# UmbilicalBoardV2.net
KiCad netlist of a schematic drawn in Altium Designer
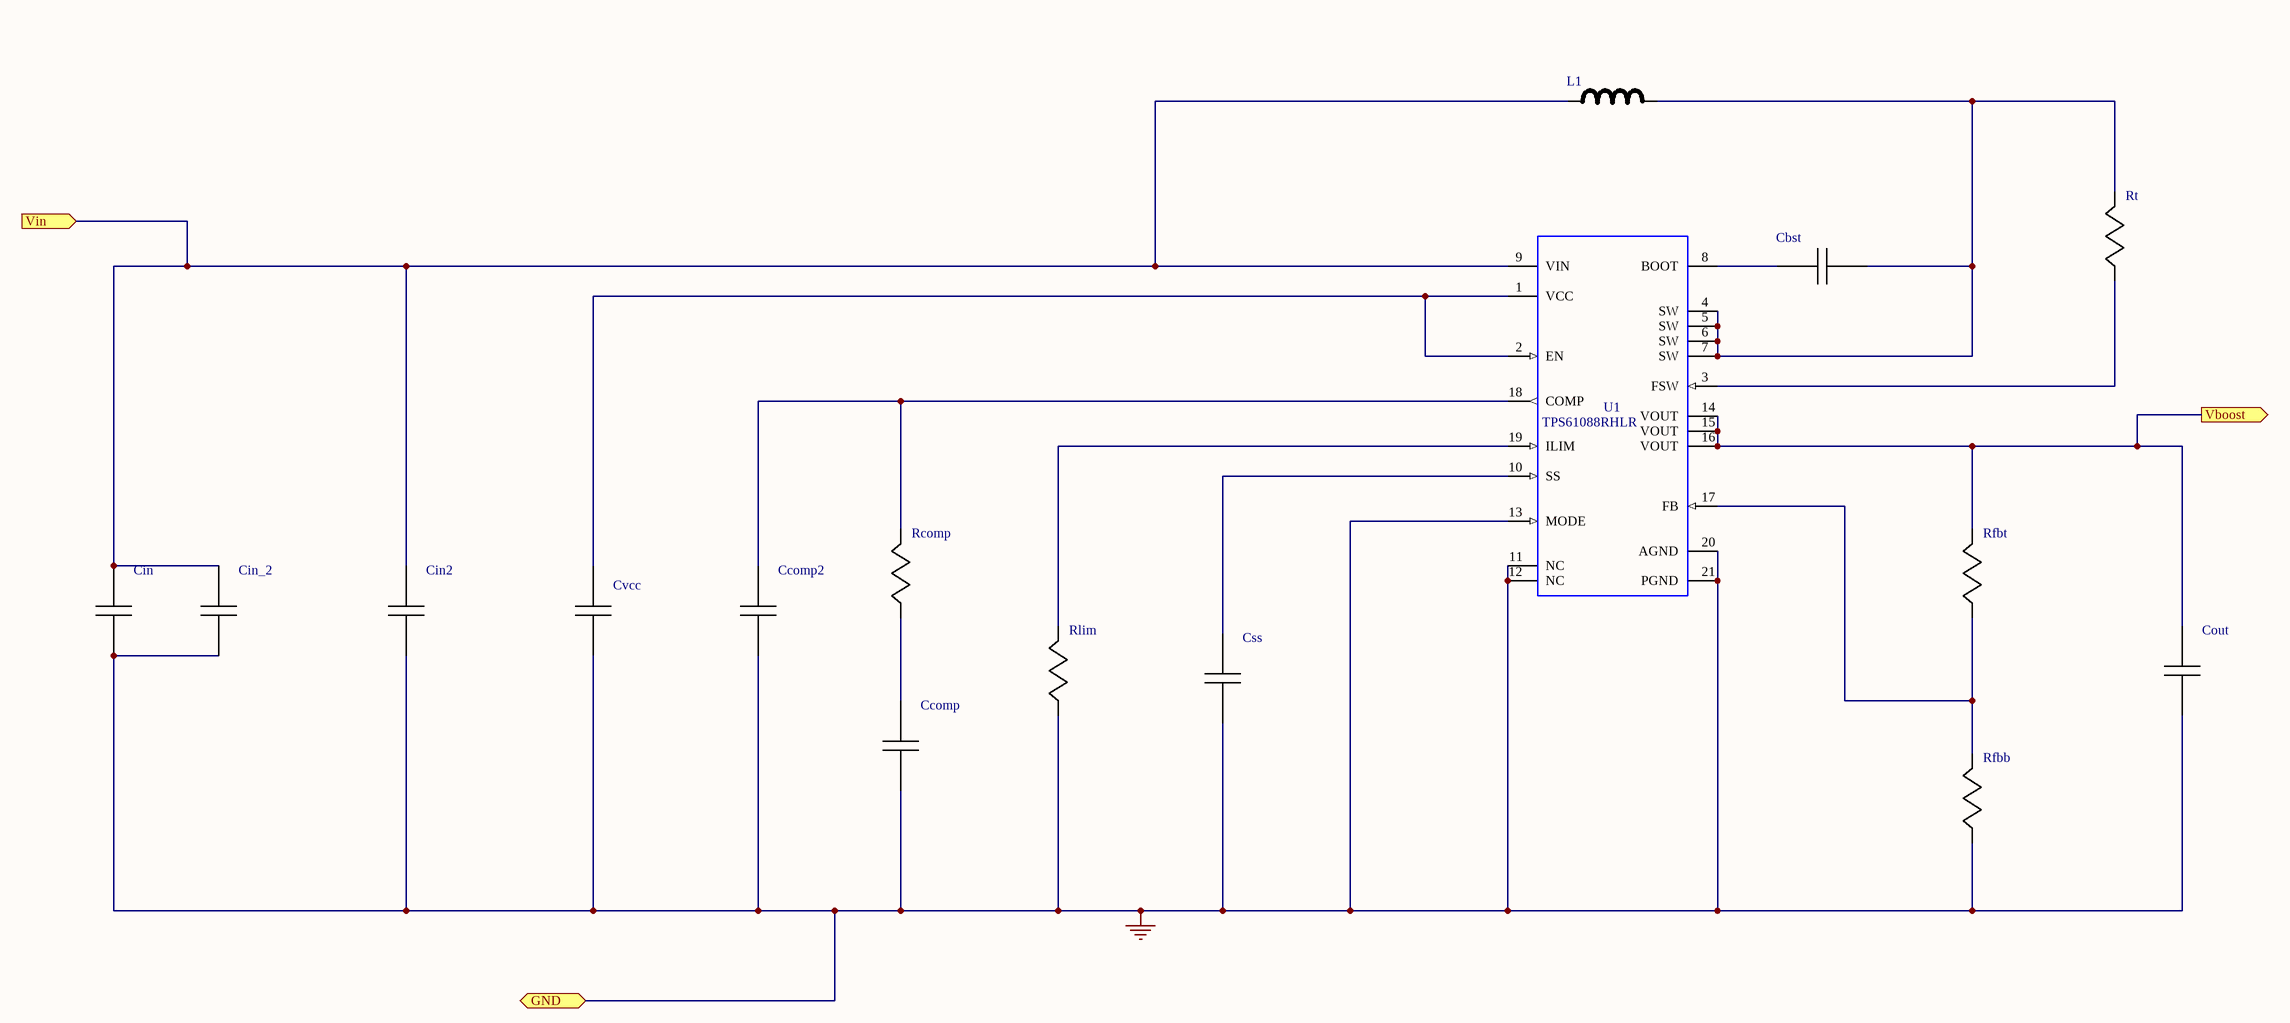
[diagram p0: UmbilicalBoardV2.schdoc]

(export (version "E")
  (design (tool "Eeschema 10.0.6"))
  (components
    (comp (ref "Cbst")
      (value "C1005X5R1A104K")
      (footprint "1005")
      (description "Imported")
      (libsource (lib "2015-10-09_12-54-35") (part "C1005X5R1A104K"))
    )
    (comp (ref "Ccomp")
      (value "02013A220GAT2A")
      (footprint "0201")
      (description "Imported")
      (libsource (lib "2015-10-09_12-54-35") (part "02013A220GAT2A"))
    )
    (comp (ref "Ccomp2")
      (value "CL02C100JO2ANNC")
      (footprint "01005")
      (description "Imported")
      (libsource (lib "2015-10-09_12-54-35") (part "CL02C100JO2ANNC"))
    )
    (comp (ref "Cin")
      (value "GRM188R61C106MA7")
      (footprint "0603")
      (description "Imported")
      (fields (field (name "MANUFACTURER_PART_NUMBER") "GRM188R61C106MA73D"))
      (libsource (lib "2015-10-09_12-54-35") (part "GRM188R61C106MA7"))
    )
    (comp (ref "Cin2")
      (value "GRM155R61C104KA8")
      (footprint "0402")
      (description "Imported")
      (fields (field (name "MANUFACTURER_PART_NUMBER") "GRM155R61C104KA88D"))
      (libsource (lib "2015-10-09_12-54-35") (part "GRM155R61C104KA8"))
    )
    (comp (ref "Cin_2")
      (value "GRM188R61C106MA7")
      (footprint "0603")
      (description "Imported")
      (fields (field (name "MANUFACTURER_PART_NUMBER") "GRM188R61C106MA73D"))
      (libsource (lib "2015-10-09_12-54-35") (part "GRM188R61C106MA7"))
    )
    (comp (ref "Cout")
      (value "C3216X5R1E226M")
      (footprint "1005")
      (description "Imported")
      (libsource (lib "2015-10-09_12-54-35") (part "C3216X5R1E226M"))
    )
    (comp (ref "Css")
      (value "GRM155R71C822KA0")
      (footprint "0402")
      (description "Imported")
      (fields (field (name "MANUFACTURER_PART_NUMBER") "GRM155R71C822KA01D"))
      (libsource (lib "2015-10-09_12-54-35") (part "GRM155R71C822KA0"))
    )
    (comp (ref "Cvcc")
      (value "C1608X5R1A105K")
      (footprint "1608")
      (description "Imported")
      (libsource (lib "2015-10-09_12-54-35") (part "C1608X5R1A105K"))
    )
    (comp (ref "L1")
      (value "XAL4020-601MEB")
      (footprint "XAL4020")
      (description "Imported")
      (libsource (lib "2015-10-09_12-54-35") (part "XAL4020-601MEB"))
    )
    (comp (ref "Rcomp")
      (value "CRCW040249K9FKED")
      (footprint "0402")
      (description "Imported")
      (libsource (lib "2015-10-09_12-54-35") (part "CRCW040249K9FKED"))
    )
    (comp (ref "Rfbb")
      (value "RC0603FR-0782KL")
      (footprint "0603")
      (description "Imported")
      (libsource (lib "2015-10-09_12-54-35") (part "RC0603FR-0782KL"))
    )
    (comp (ref "Rfbt")
      (value "CRCW0402732KFKED")
      (footprint "0402")
      (description "Imported")
      (libsource (lib "2015-10-09_12-54-35") (part "CRCW0402732KFKED"))
    )
    (comp (ref "Rlim")
      (value "ERJ-8ENF1133V")
      (footprint "1206")
      (description "Imported")
      (libsource (lib "2015-10-09_12-54-35") (part "ERJ-8ENF1133V"))
    )
    (comp (ref "Rt")
      (value "RC1206FR-0782KL")
      (footprint "1206")
      (description "Imported")
      (libsource (lib "2015-10-09_12-54-35") (part "RC1206FR-0782KL"))
    )
    (comp (ref "U1")
      (value "TPS61088RHLR")
      (footprint "RHL0020A")
      (fields (field (name "PACKAGEREFERENCE") "TPS61088RHLR"))
      (libsource (lib "TI WEBENCH") (part "U1"))
    )
  )
  (nets
    (net (code "1") (name "/Vboost") (class "Default")
      (node (ref "Cout") (pin "1") (pinfunction "1_1") (pintype "passive"))
      (node (ref "Rfbt") (pin "1") (pinfunction "1_1") (pintype "passive"))
      (node (ref "U1") (pin "14") (pinfunction "VOUT_14") (pintype "power_in"))
      (node (ref "U1") (pin "15") (pinfunction "VOUT_15") (pintype "power_in"))
      (node (ref "U1") (pin "16") (pinfunction "VOUT_16") (pintype "power_in"))
    )
    (net (code "2") (name "/Vin") (class "Default")
      (node (ref "Cin") (pin "1") (pinfunction "1_1") (pintype "passive"))
      (node (ref "Cin2") (pin "1") (pinfunction "1_1") (pintype "passive"))
      (node (ref "Cin_2") (pin "1") (pinfunction "1_1") (pintype "passive"))
      (node (ref "L1") (pin "1") (pinfunction "1_1") (pintype "passive"))
      (node (ref "U1") (pin "9") (pinfunction "VIN_9") (pintype "power_in"))
    )
    (net (code "3") (name "0") (class "Default")
      (node (ref "Ccomp") (pin "2") (pinfunction "2_2") (pintype "passive"))
      (node (ref "Ccomp2") (pin "1") (pinfunction "1_1") (pintype "passive"))
      (node (ref "Cin") (pin "2") (pinfunction "2_2") (pintype "passive"))
      (node (ref "Cin2") (pin "2") (pinfunction "2_2") (pintype "passive"))
      (node (ref "Cin_2") (pin "2") (pinfunction "2_2") (pintype "passive"))
      (node (ref "Cout") (pin "2") (pinfunction "2_2") (pintype "passive"))
      (node (ref "Css") (pin "1") (pinfunction "1_1") (pintype "passive"))
      (node (ref "Cvcc") (pin "1") (pinfunction "1_1") (pintype "passive"))
      (node (ref "Rfbb") (pin "2") (pinfunction "2_2") (pintype "passive"))
      (node (ref "Rlim") (pin "2") (pinfunction "2_2") (pintype "passive"))
      (node (ref "U1") (pin "11") (pinfunction "NC_11") (pintype "passive"))
      (node (ref "U1") (pin "12") (pinfunction "NC_12") (pintype "passive"))
      (node (ref "U1") (pin "13") (pinfunction "MODE_13") (pintype "input"))
      (node (ref "U1") (pin "20") (pinfunction "AGND_20") (pintype "power_in"))
      (node (ref "U1") (pin "21") (pinfunction "PGND_21") (pintype "power_in"))
    )
    (net (code "4") (name "Net-(Cbst-Pad1)") (class "Default")
      (node (ref "Cbst") (pin "1") (pinfunction "1_1") (pintype "passive"))
      (node (ref "L1") (pin "2") (pinfunction "2_2") (pintype "passive"))
      (node (ref "Rt") (pin "1") (pinfunction "1_1") (pintype "passive"))
      (node (ref "U1") (pin "4") (pinfunction "SW_4") (pintype "power_in"))
      (node (ref "U1") (pin "5") (pinfunction "SW_5") (pintype "power_in"))
      (node (ref "U1") (pin "6") (pinfunction "SW_6") (pintype "power_in"))
      (node (ref "U1") (pin "7") (pinfunction "SW_7") (pintype "power_in"))
    )
    (net (code "5") (name "Net-(Ccomp-Pad1)") (class "Default")
      (node (ref "Ccomp") (pin "1") (pinfunction "1_1") (pintype "passive"))
      (node (ref "Rcomp") (pin "2") (pinfunction "2_2") (pintype "passive"))
    )
    (net (code "6") (name "Net-(U1-BOOT)") (class "Default")
      (node (ref "Cbst") (pin "2") (pinfunction "2_2") (pintype "passive"))
      (node (ref "U1") (pin "8") (pinfunction "BOOT_8") (pintype "power_in"))
    )
    (net (code "7") (name "Net-(U1-COMP)") (class "Default")
      (node (ref "Ccomp2") (pin "2") (pinfunction "2_2") (pintype "passive"))
      (node (ref "Rcomp") (pin "1") (pinfunction "1_1") (pintype "passive"))
      (node (ref "U1") (pin "18") (pinfunction "COMP_18") (pintype "output"))
    )
    (net (code "8") (name "Net-(U1-EN)") (class "Default")
      (node (ref "Cvcc") (pin "2") (pinfunction "2_2") (pintype "passive"))
      (node (ref "U1") (pin "1") (pinfunction "VCC_1") (pintype "power_in"))
      (node (ref "U1") (pin "2") (pinfunction "EN_2") (pintype "input"))
    )
    (net (code "9") (name "Net-(U1-FB)") (class "Default")
      (node (ref "Rfbb") (pin "1") (pinfunction "1_1") (pintype "passive"))
      (node (ref "Rfbt") (pin "2") (pinfunction "2_2") (pintype "passive"))
      (node (ref "U1") (pin "17") (pinfunction "FB_17") (pintype "input"))
    )
    (net (code "10") (name "Net-(U1-FSW)") (class "Default")
      (node (ref "Rt") (pin "2") (pinfunction "2_2") (pintype "passive"))
      (node (ref "U1") (pin "3") (pinfunction "FSW_3") (pintype "input"))
    )
    (net (code "11") (name "Net-(U1-ILIM)") (class "Default")
      (node (ref "Rlim") (pin "1") (pinfunction "1_1") (pintype "passive"))
      (node (ref "U1") (pin "19") (pinfunction "ILIM_19") (pintype "input"))
    )
    (net (code "12") (name "Net-(U1-SS)") (class "Default")
      (node (ref "Css") (pin "2") (pinfunction "2_2") (pintype "passive"))
      (node (ref "U1") (pin "10") (pinfunction "SS_10") (pintype "input"))
    )
  )
)
